# Project.net
KiCad netlist of a schematic drawn in EasyEDA Pro
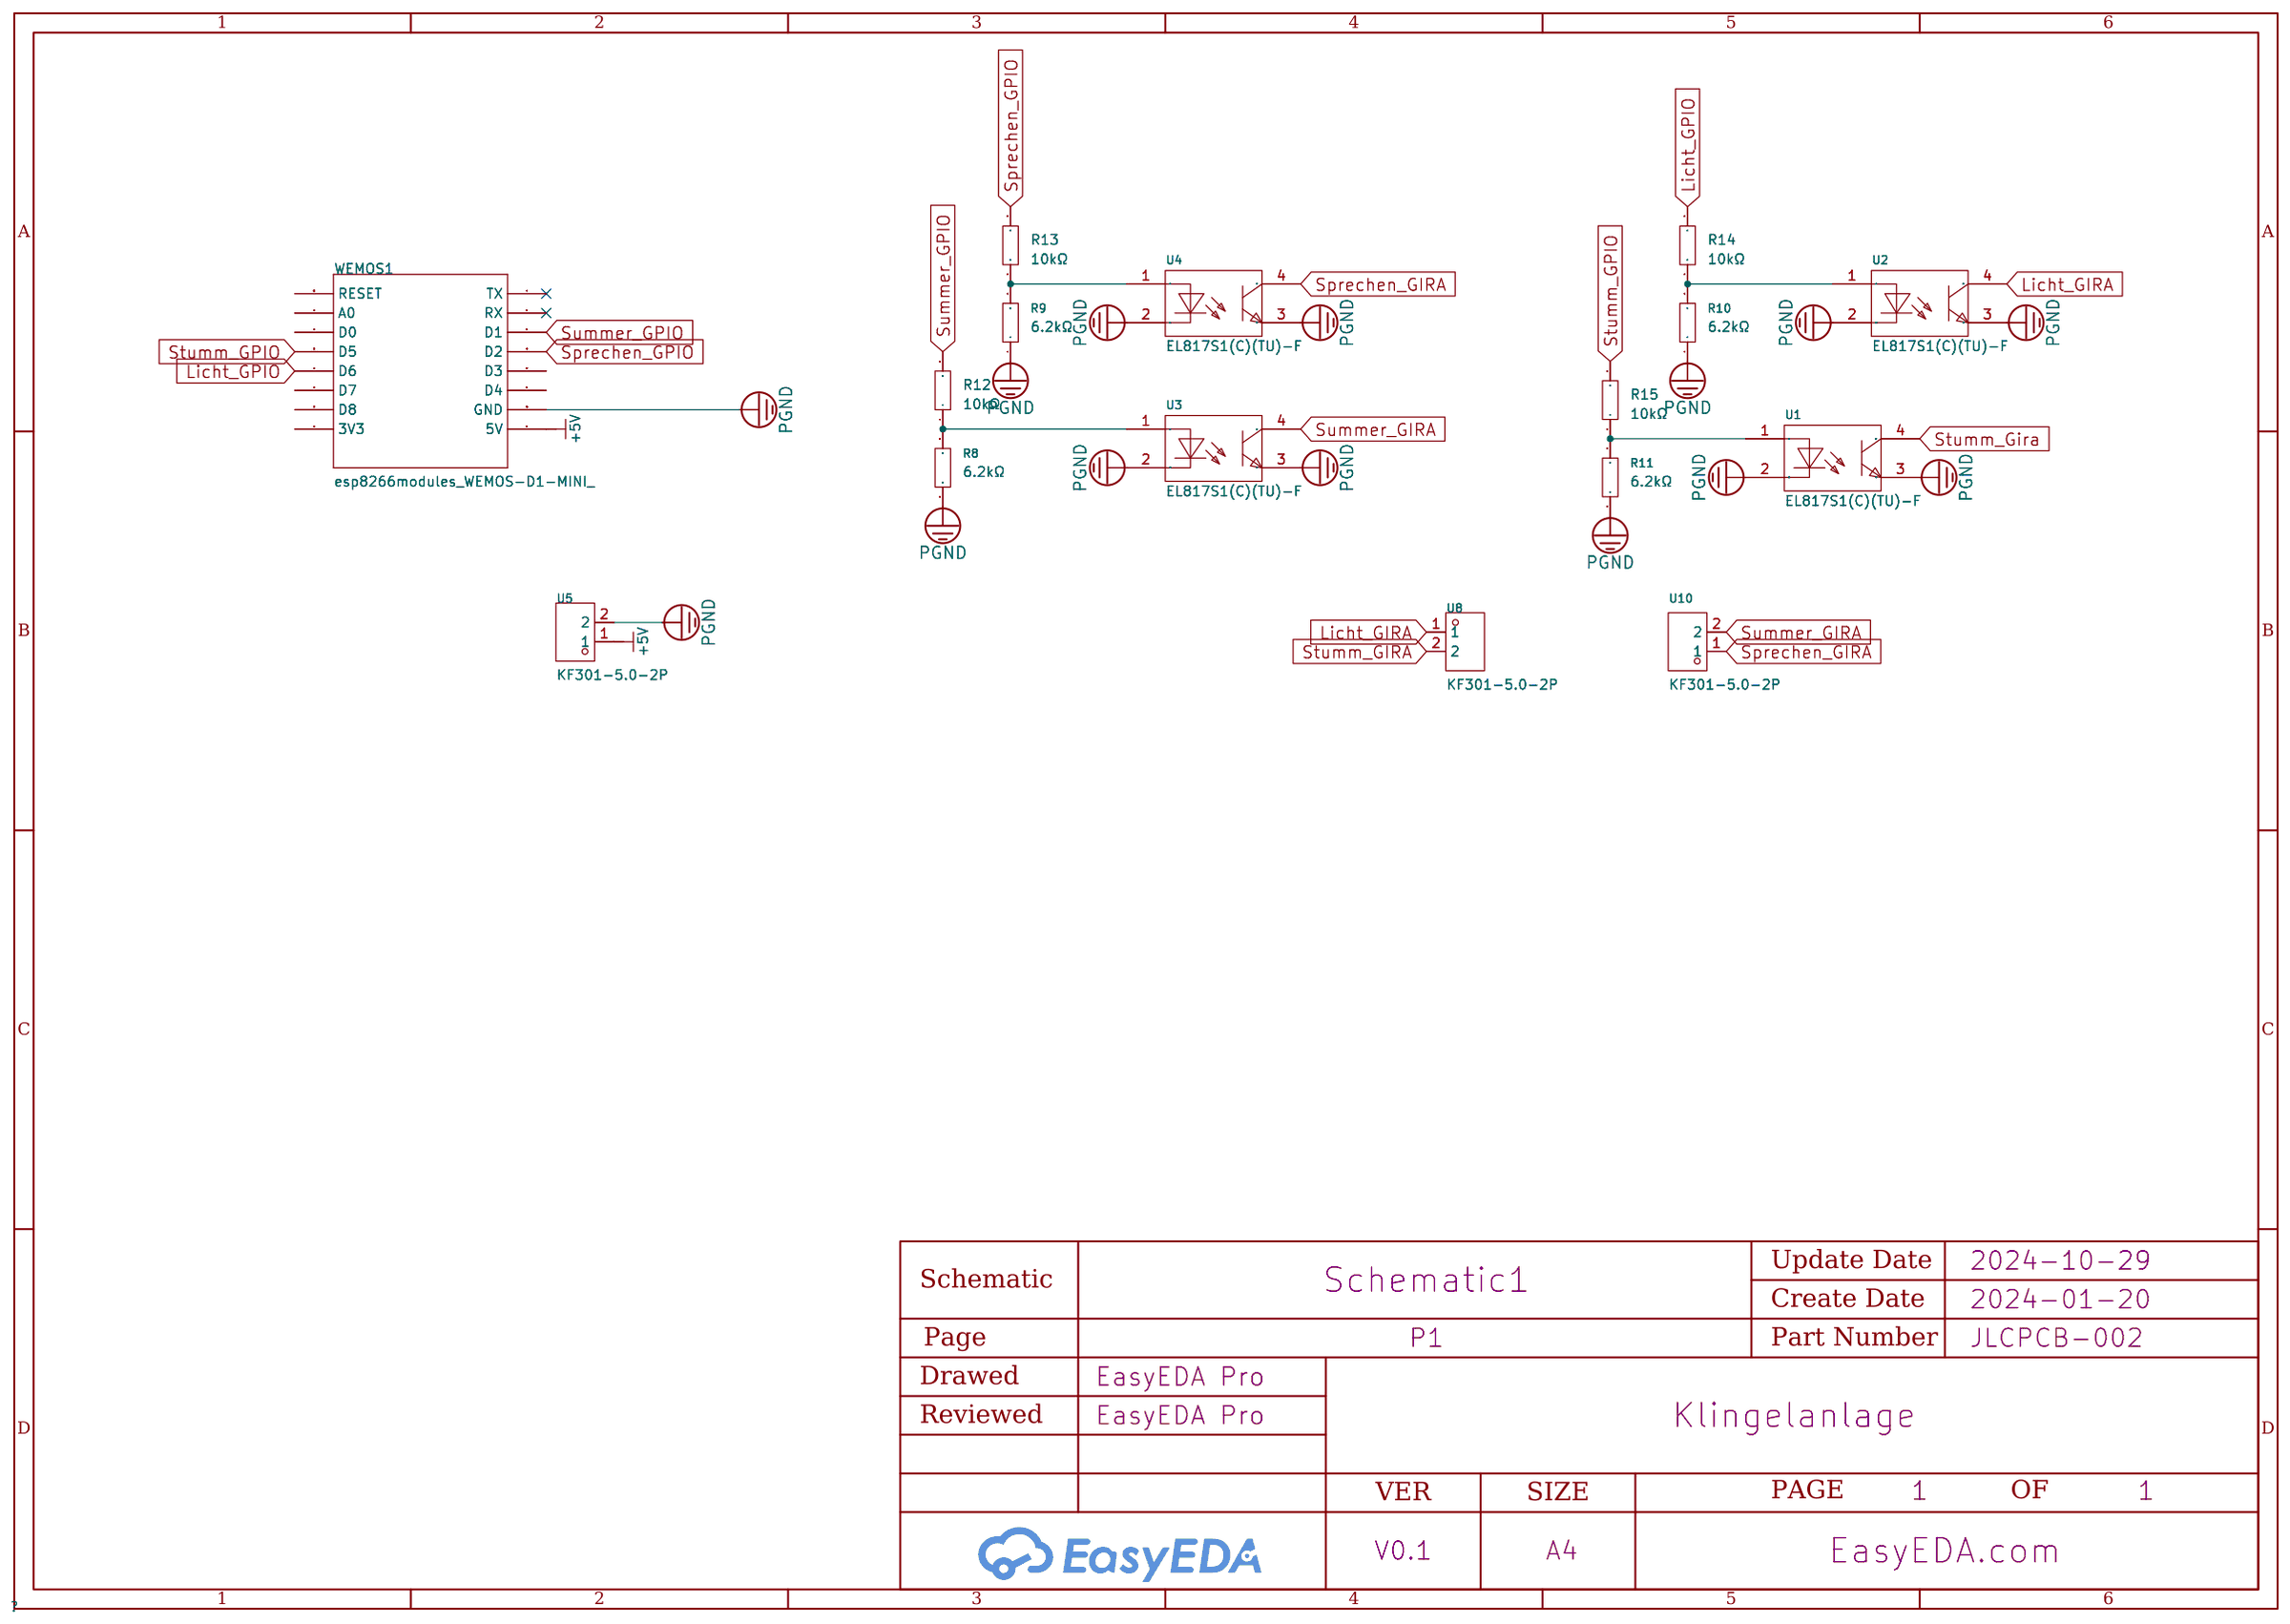
[diagram p0: schematic sheet]

(export (version "E")
  (design (tool "Eeschema 10.0.6"))
  (components
    (comp (ref "R8")
      (value "6.2kΩ")
      (footprint "easyedapro:R0603")
      (fields (field (name "Manufacturer Part") "RMC06036.2K1%N") (field (name "Manufacturer") "Tyohm(幸亚电阻)"))
      (libsource (lib "easyedapro") (part "RMC06036.2K1%N"))
    )
    (comp (ref "R9")
      (value "6.2kΩ")
      (footprint "easyedapro:R0603")
      (fields (field (name "Manufacturer Part") "RMC06036.2K1%N") (field (name "Manufacturer") "Tyohm(幸亚电阻)"))
      (libsource (lib "easyedapro") (part "RMC06036.2K1%N"))
    )
    (comp (ref "R10")
      (value "6.2kΩ")
      (footprint "easyedapro:R0603")
      (fields (field (name "Manufacturer Part") "RMC06036.2K1%N") (field (name "Manufacturer") "Tyohm(幸亚电阻)"))
      (libsource (lib "easyedapro") (part "RMC06036.2K1%N"))
    )
    (comp (ref "R11")
      (value "6.2kΩ")
      (footprint "easyedapro:R0603")
      (fields (field (name "Manufacturer Part") "RMC06036.2K1%N") (field (name "Manufacturer") "Tyohm(幸亚电阻)"))
      (libsource (lib "easyedapro") (part "RMC06036.2K1%N"))
    )
    (comp (ref "R12")
      (value "10kΩ")
      (footprint "easyedapro:R0603")
      (fields (field (name "Manufacturer Part") "RC0603FR-0710KL") (field (name "Manufacturer") "YAGEO(国巨)"))
      (libsource (lib "easyedapro") (part "RC0603FR-0710KL"))
    )
    (comp (ref "R13")
      (value "10kΩ")
      (footprint "easyedapro:R0603")
      (fields (field (name "Manufacturer Part") "RC0603FR-0710KL") (field (name "Manufacturer") "YAGEO(国巨)"))
      (libsource (lib "easyedapro") (part "RC0603FR-0710KL"))
    )
    (comp (ref "R14")
      (value "10kΩ")
      (footprint "easyedapro:R0603")
      (fields (field (name "Manufacturer Part") "RC0603FR-0710KL") (field (name "Manufacturer") "YAGEO(国巨)"))
      (libsource (lib "easyedapro") (part "RC0603FR-0710KL"))
    )
    (comp (ref "R15")
      (value "10kΩ")
      (footprint "easyedapro:R0603")
      (fields (field (name "Manufacturer Part") "RC0603FR-0710KL") (field (name "Manufacturer") "YAGEO(国巨)"))
      (libsource (lib "easyedapro") (part "RC0603FR-0710KL"))
    )
    (comp (ref "U1")
      (value "EL817S1(C)(TU)-F")
      (footprint "easyedapro:OPTO-SMD-4_L4.6-W6.5-P2.54-LS10.3-TL")
      (fields (field (name "Manufacturer") "EVERLIGHT(亿光)"))
      (libsource (lib "easyedapro") (part "EL817S1(C)(TU)-F"))
    )
    (comp (ref "U2")
      (value "EL817S1(C)(TU)-F")
      (footprint "easyedapro:OPTO-SMD-4_L4.6-W6.5-P2.54-LS10.3-TL")
      (fields (field (name "Manufacturer") "EVERLIGHT(亿光)"))
      (libsource (lib "easyedapro") (part "EL817S1(C)(TU)-F"))
    )
    (comp (ref "U3")
      (value "EL817S1(C)(TU)-F")
      (footprint "easyedapro:OPTO-SMD-4_L4.6-W6.5-P2.54-LS10.3-TL")
      (fields (field (name "Manufacturer") "EVERLIGHT(亿光)"))
      (libsource (lib "easyedapro") (part "EL817S1(C)(TU)-F"))
    )
    (comp (ref "U4")
      (value "EL817S1(C)(TU)-F")
      (footprint "easyedapro:OPTO-SMD-4_L4.6-W6.5-P2.54-LS10.3-TL")
      (fields (field (name "Manufacturer") "EVERLIGHT(亿光)"))
      (libsource (lib "easyedapro") (part "EL817S1(C)(TU)-F"))
    )
    (comp (ref "U5")
      (value "KF301-5.0-2P")
      (footprint "easyedapro:CONN-TH_P5.00_KF301-5.0-2P")
      (fields (field (name "Manufacturer") "KEFA(科发)"))
      (libsource (lib "easyedapro") (part "KF301-5.0-2P"))
    )
    (comp (ref "U8")
      (value "KF301-5.0-2P")
      (footprint "easyedapro:CONN-TH_P5.00_KF301-5.0-2P")
      (fields (field (name "Manufacturer") "KEFA(科发)"))
      (libsource (lib "easyedapro") (part "KF301-5.0-2P"))
    )
    (comp (ref "U10")
      (value "KF301-5.0-2P")
      (footprint "easyedapro:CONN-TH_P5.00_KF301-5.0-2P")
      (fields (field (name "Manufacturer") "KEFA(科发)"))
      (libsource (lib "easyedapro") (part "KF301-5.0-2P"))
    )
    (comp (ref "WEMOS1")
      (value "esp8266modules_WEMOS-D1-MINI_")
      (footprint "easyedapro:WEMOS-D1-MINI")
      (libsource (lib "easyedapro") (part "esp8266modules_WEMOS-D1-MINI_"))
    )
  )
  (nets
    (net (code "1") (name "+5V") (class "Default")
      (node (ref "U5") (pin "1") (pinfunction "1_1") (pintype "input"))
      (node (ref "WEMOS1") (pin "5V") (pinfunction "5V_5V") (pintype "input"))
    )
    (net (code "2") (name "Licht_GIRA") (class "Default")
      (node (ref "U2") (pin "4") (pinfunction "COL_4") (pintype "input"))
      (node (ref "U8") (pin "1") (pinfunction "1_1") (pintype "input"))
    )
    (net (code "3") (name "Licht_GPIO") (class "Default")
      (node (ref "R14") (pin "2") (pinfunction "2_2") (pintype "input"))
      (node (ref "WEMOS1") (pin "D6") (pinfunction "D6_D6") (pintype "input"))
    )
    (net (code "4") (name "Net-(U1-AN)") (class "Default")
      (node (ref "R11") (pin "2") (pinfunction "2_2") (pintype "input"))
      (node (ref "R15") (pin "1") (pinfunction "1_1") (pintype "input"))
      (node (ref "U1") (pin "1") (pinfunction "AN_1") (pintype "input"))
    )
    (net (code "5") (name "Net-(U2-AN)") (class "Default")
      (node (ref "R10") (pin "2") (pinfunction "2_2") (pintype "input"))
      (node (ref "R14") (pin "1") (pinfunction "1_1") (pintype "input"))
      (node (ref "U2") (pin "1") (pinfunction "AN_1") (pintype "input"))
    )
    (net (code "6") (name "Net-(U3-AN)") (class "Default")
      (node (ref "R12") (pin "1") (pinfunction "1_1") (pintype "input"))
      (node (ref "R8") (pin "2") (pinfunction "2_2") (pintype "input"))
      (node (ref "U3") (pin "1") (pinfunction "AN_1") (pintype "input"))
    )
    (net (code "7") (name "Net-(U4-AN)") (class "Default")
      (node (ref "R13") (pin "1") (pinfunction "1_1") (pintype "input"))
      (node (ref "R9") (pin "2") (pinfunction "2_2") (pintype "input"))
      (node (ref "U4") (pin "1") (pinfunction "AN_1") (pintype "input"))
    )
    (net (code "8") (name "PGND") (class "Default")
      (node (ref "R10") (pin "1") (pinfunction "1_1") (pintype "input"))
      (node (ref "R11") (pin "1") (pinfunction "1_1") (pintype "input"))
      (node (ref "R8") (pin "1") (pinfunction "1_1") (pintype "input"))
      (node (ref "R9") (pin "1") (pinfunction "1_1") (pintype "input"))
      (node (ref "U1") (pin "2") (pinfunction "CAT_2") (pintype "input"))
      (node (ref "U1") (pin "3") (pinfunction "EM_3") (pintype "input"))
      (node (ref "U2") (pin "2") (pinfunction "CAT_2") (pintype "input"))
      (node (ref "U2") (pin "3") (pinfunction "EM_3") (pintype "input"))
      (node (ref "U3") (pin "2") (pinfunction "CAT_2") (pintype "input"))
      (node (ref "U3") (pin "3") (pinfunction "EM_3") (pintype "input"))
      (node (ref "U4") (pin "2") (pinfunction "CAT_2") (pintype "input"))
      (node (ref "U4") (pin "3") (pinfunction "EM_3") (pintype "input"))
      (node (ref "U5") (pin "2") (pinfunction "2_2") (pintype "input"))
      (node (ref "WEMOS1") (pin "GND") (pinfunction "GND_GND") (pintype "input"))
    )
    (net (code "9") (name "Sprechen_GIRA") (class "Default")
      (node (ref "U10") (pin "1") (pinfunction "1_1") (pintype "input"))
      (node (ref "U4") (pin "4") (pinfunction "COL_4") (pintype "input"))
    )
    (net (code "10") (name "Sprechen_GPIO") (class "Default")
      (node (ref "R13") (pin "2") (pinfunction "2_2") (pintype "input"))
      (node (ref "WEMOS1") (pin "D2") (pinfunction "D2_D2") (pintype "input"))
    )
    (net (code "11") (name "Stumm_GIRA") (class "Default")
      (node (ref "U8") (pin "2") (pinfunction "2_2") (pintype "input"))
    )
    (net (code "12") (name "Stumm_GPIO") (class "Default")
      (node (ref "R15") (pin "2") (pinfunction "2_2") (pintype "input"))
      (node (ref "WEMOS1") (pin "D5") (pinfunction "D5_D5") (pintype "input"))
    )
    (net (code "13") (name "Stumm_Gira") (class "Default")
      (node (ref "U1") (pin "4") (pinfunction "COL_4") (pintype "input"))
    )
    (net (code "14") (name "Summer_GIRA") (class "Default")
      (node (ref "U10") (pin "2") (pinfunction "2_2") (pintype "input"))
      (node (ref "U3") (pin "4") (pinfunction "COL_4") (pintype "input"))
    )
    (net (code "15") (name "Summer_GPIO") (class "Default")
      (node (ref "R12") (pin "2") (pinfunction "2_2") (pintype "input"))
      (node (ref "WEMOS1") (pin "D1") (pinfunction "D1_D1") (pintype "input"))
    )
    (net (code "16") (name "unconnected-(WEMOS1-Pad3V3)") (class "Default")
      (node (ref "WEMOS1") (pin "3V3") (pinfunction "3V3_3V3") (pintype "input"))
    )
    (net (code "17") (name "unconnected-(WEMOS1-PadA0)") (class "Default")
      (node (ref "WEMOS1") (pin "A0") (pinfunction "A0_A0") (pintype "input"))
    )
    (net (code "18") (name "unconnected-(WEMOS1-PadD0)") (class "Default")
      (node (ref "WEMOS1") (pin "D0") (pinfunction "D0_D0") (pintype "input"))
    )
    (net (code "19") (name "unconnected-(WEMOS1-PadD3)") (class "Default")
      (node (ref "WEMOS1") (pin "D3") (pinfunction "D3_D3") (pintype "input"))
    )
    (net (code "20") (name "unconnected-(WEMOS1-PadD4)") (class "Default")
      (node (ref "WEMOS1") (pin "D4") (pinfunction "D4_D4") (pintype "input"))
    )
    (net (code "21") (name "unconnected-(WEMOS1-PadD7)") (class "Default")
      (node (ref "WEMOS1") (pin "D7") (pinfunction "D7_D7") (pintype "input"))
    )
    (net (code "22") (name "unconnected-(WEMOS1-PadD8)") (class "Default")
      (node (ref "WEMOS1") (pin "D8") (pinfunction "D8_D8") (pintype "input"))
    )
    (net (code "23") (name "unconnected-(WEMOS1-PadRESET)") (class "Default")
      (node (ref "WEMOS1") (pin "RESET") (pinfunction "RESET_RESET") (pintype "input"))
    )
    (net (code "24") (name "unconnected-(WEMOS1-PadRX)") (class "Default")
      (node (ref "WEMOS1") (pin "RX") (pinfunction "RX_RX") (pintype "input+no_connect"))
    )
    (net (code "25") (name "unconnected-(WEMOS1-PadTX)") (class "Default")
      (node (ref "WEMOS1") (pin "TX") (pinfunction "TX_TX") (pintype "input+no_connect"))
    )
  )
)
